# Supply.net
KiCad netlist of a schematic drawn in Altium Designer
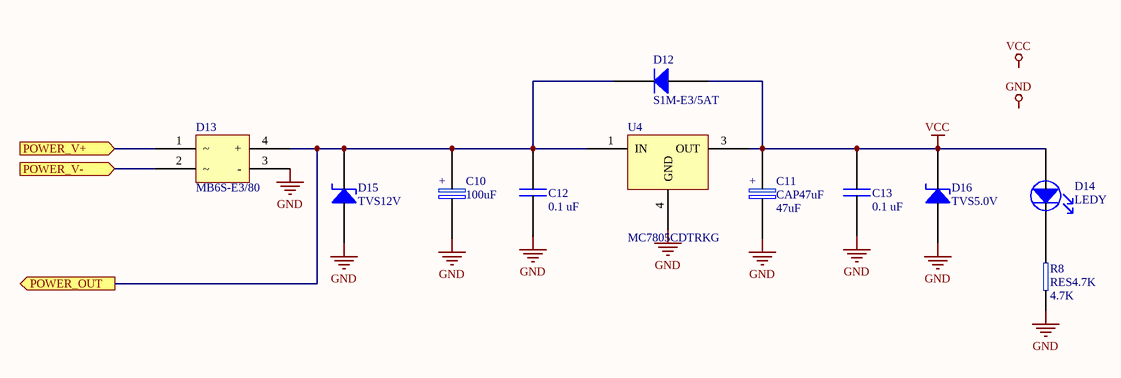
[diagram p0: Supply.SchDoc]

(export (version "E")
  (design (tool "Eeschema 10.0.6"))
  (components
    (comp (ref "C10")
      (value "100uF")
      (footprint "techdev:EEH-ZA1E101XP")
      (description "Capacitores de polímero orgánico de aluminio 100uF 25volts 6.3x7.7mm")
      (fields (field (name "MPN") "EEH-ZA1E101XP") (field (name "Comment") "CAP100uF"))
      (libsource (lib "Miscellaneous Devices") (part "CAP100uF"))
    )
    (comp (ref "C11")
      (value "CAP47uF")
      (footprint "EEH-ZA1E101XP")
      (description "Capacitores de polímero orgánico de aluminio 25volts 47uF ESR 30mohm")
      (fields (field (name "MPN") "25SVPF47M") (field (name "ALTIUM_VALUE") "47uF"))
      (libsource (lib "Miscellaneous Devices") (part "CAP47uF"))
    )
    (comp (ref "C12")
      (value "0.1 uF")
      (footprint "techdev:CAP0603")
      (description "Capacitores cerámicos de capas múltiples (MLCC) - SMD/SMT 0603 0.1uF 16volts X7R 5%")
      (fields (field (name "MPN") "VJ0603Y104JXJPW1BC") (field (name "Comment") "CAP0.1uF"))
      (libsource (lib "Miscellaneous Devices") (part "C0.1UF"))
    )
    (comp (ref "C13")
      (value "0.1 uF")
      (footprint "techdev:CAP0603")
      (description "Capacitores cerámicos de capas múltiples (MLCC) - SMD/SMT 0603 0.1uF 16volts X7R 5%")
      (fields (field (name "MPN") "VJ0603Y104JXJPW1BC") (field (name "Comment") "CAP0.1uF"))
      (libsource (lib "Miscellaneous Devices") (part "C0.1UF"))
    )
    (comp (ref "D12")
      (value "S1M-E3/5AT")
      (footprint "techdev:S1M-E3/5AT")
      (description "Rectificadores 1.0 Amp 1000 Volt 30A IFSM @ 8.3ms")
      (libsource (lib "Miscellaneous Devices") (part "S1M-E3/5AT"))
    )
    (comp (ref "D13")
      (value "MB6S-E3/80")
      (footprint "techdev:MB6S-E3/80")
      (description "Rectificadores en puente 600 Volt 0.5 Amp 35 Amp IFSM")
      (libsource (lib "Miscellaneous Devices") (part "MB6S-E3/80"))
    )
    (comp (ref "D14")
      (value "LEDY")
      (footprint "150060YS75000")
      (description "LED estándar - SMD (montaje superficial) WL-SMCW SMDMono TpVw Waterclr 0603 Yellow")
      (fields (field (name "MPN") "150060YS75000"))
      (libsource (lib "techdev") (part "LEDY"))
    )
    (comp (ref "D15")
      (value "TVS12V")
      (footprint "SMBJ5.0A")
      (description "Diodos TVS - Supresores de tensión transitoria 600W 12V 5% Uni")
      (fields (field (name "MPN") "SMBJ12A-E3/52"))
      (libsource (lib "Miscellaneous Devices") (part "TVS12V"))
    )
    (comp (ref "D16")
      (value "TVS5.0V")
      (footprint "SMBJ5.0A")
      (description "Diodos TVS - Supresores de tensión transitoria 5Vr 600W 65.3A 5% UniDirectional")
      (fields (field (name "MPN") "SMBJ5.0A"))
      (libsource (lib "Miscellaneous Devices") (part "TVS5.0V"))
    )
    (comp (ref "R8")
      (value "RES4.7K")
      (footprint "RES0603")
      (description "Resistores de película gruesa - SMD 1/10watt 4.7Kohms 1%")
      (fields (field (name "MPN") "CRCW06034K70FKEA") (field (name "ALTIUM_VALUE") "4.7K"))
      (libsource (lib "Miscellaneous Devices") (part "RES4.7K"))
    )
    (comp (ref "U4")
      (value "MC7805CDTRKG")
      (footprint "techdev:MC7805CDTRKG")
      (description "Reguladores de tensión lineal 5V 1A Postive")
      (libsource (lib "Miscellaneous Devices") (part "MC7805CDTRKG"))
    )
  )
  (nets
    (net (code "1") (name "/POWER_OUT") (class "Default")
      (node (ref "C10") (pin "1") (pinfunction "pos_1") (pintype "passive"))
      (node (ref "C12") (pin "1") (pintype "passive"))
      (node (ref "D12") (pin "1") (pinfunction "Cathode_1") (pintype "passive"))
      (node (ref "D13") (pin "4") (pinfunction "+_4") (pintype "passive"))
      (node (ref "D15") (pin "1") (pinfunction "Cathode_1") (pintype "passive"))
      (node (ref "U4") (pin "1") (pinfunction "IN_1") (pintype "passive"))
    )
    (net (code "2") (name "/POWER_V+") (class "Default")
      (node (ref "D13") (pin "1") (pinfunction "~_1") (pintype "passive"))
    )
    (net (code "3") (name "/POWER_V-") (class "Default")
      (node (ref "D13") (pin "2") (pinfunction "~_2") (pintype "passive"))
    )
    (net (code "4") (name "GND") (class "Default")
      (node (ref "C10") (pin "2") (pinfunction "neg_2") (pintype "passive"))
      (node (ref "C11") (pin "2") (pinfunction "neg_2") (pintype "passive"))
      (node (ref "C12") (pin "2") (pintype "passive"))
      (node (ref "C13") (pin "2") (pintype "passive"))
      (node (ref "D13") (pin "3") (pinfunction "-_3") (pintype "passive"))
      (node (ref "D15") (pin "2") (pinfunction "Anode_2") (pintype "passive"))
      (node (ref "D16") (pin "2") (pinfunction "Anode_2") (pintype "passive"))
      (node (ref "R8") (pin "2") (pinfunction "neg_2") (pintype "passive"))
      (node (ref "U4") (pin "4") (pinfunction "GND_4") (pintype "passive"))
    )
    (net (code "5") (name "Net-(D14-Cathode)") (class "Default")
      (node (ref "D14") (pin "1") (pinfunction "Cathode_1") (pintype "passive"))
      (node (ref "R8") (pin "1") (pinfunction "pos_1") (pintype "passive"))
    )
    (net (code "6") (name "VCC") (class "Default")
      (node (ref "C11") (pin "1") (pinfunction "pos_1") (pintype "passive"))
      (node (ref "C13") (pin "1") (pintype "passive"))
      (node (ref "D12") (pin "2") (pinfunction "Anode_2") (pintype "passive"))
      (node (ref "D14") (pin "2") (pinfunction "Anode_2") (pintype "passive"))
      (node (ref "D16") (pin "1") (pinfunction "Cathode_1") (pintype "passive"))
      (node (ref "U4") (pin "3") (pinfunction "OUT_3") (pintype "passive"))
    )
  )
)
